# ComboSensorBreakout.net
KiCad netlist of a schematic drawn in EAGLE
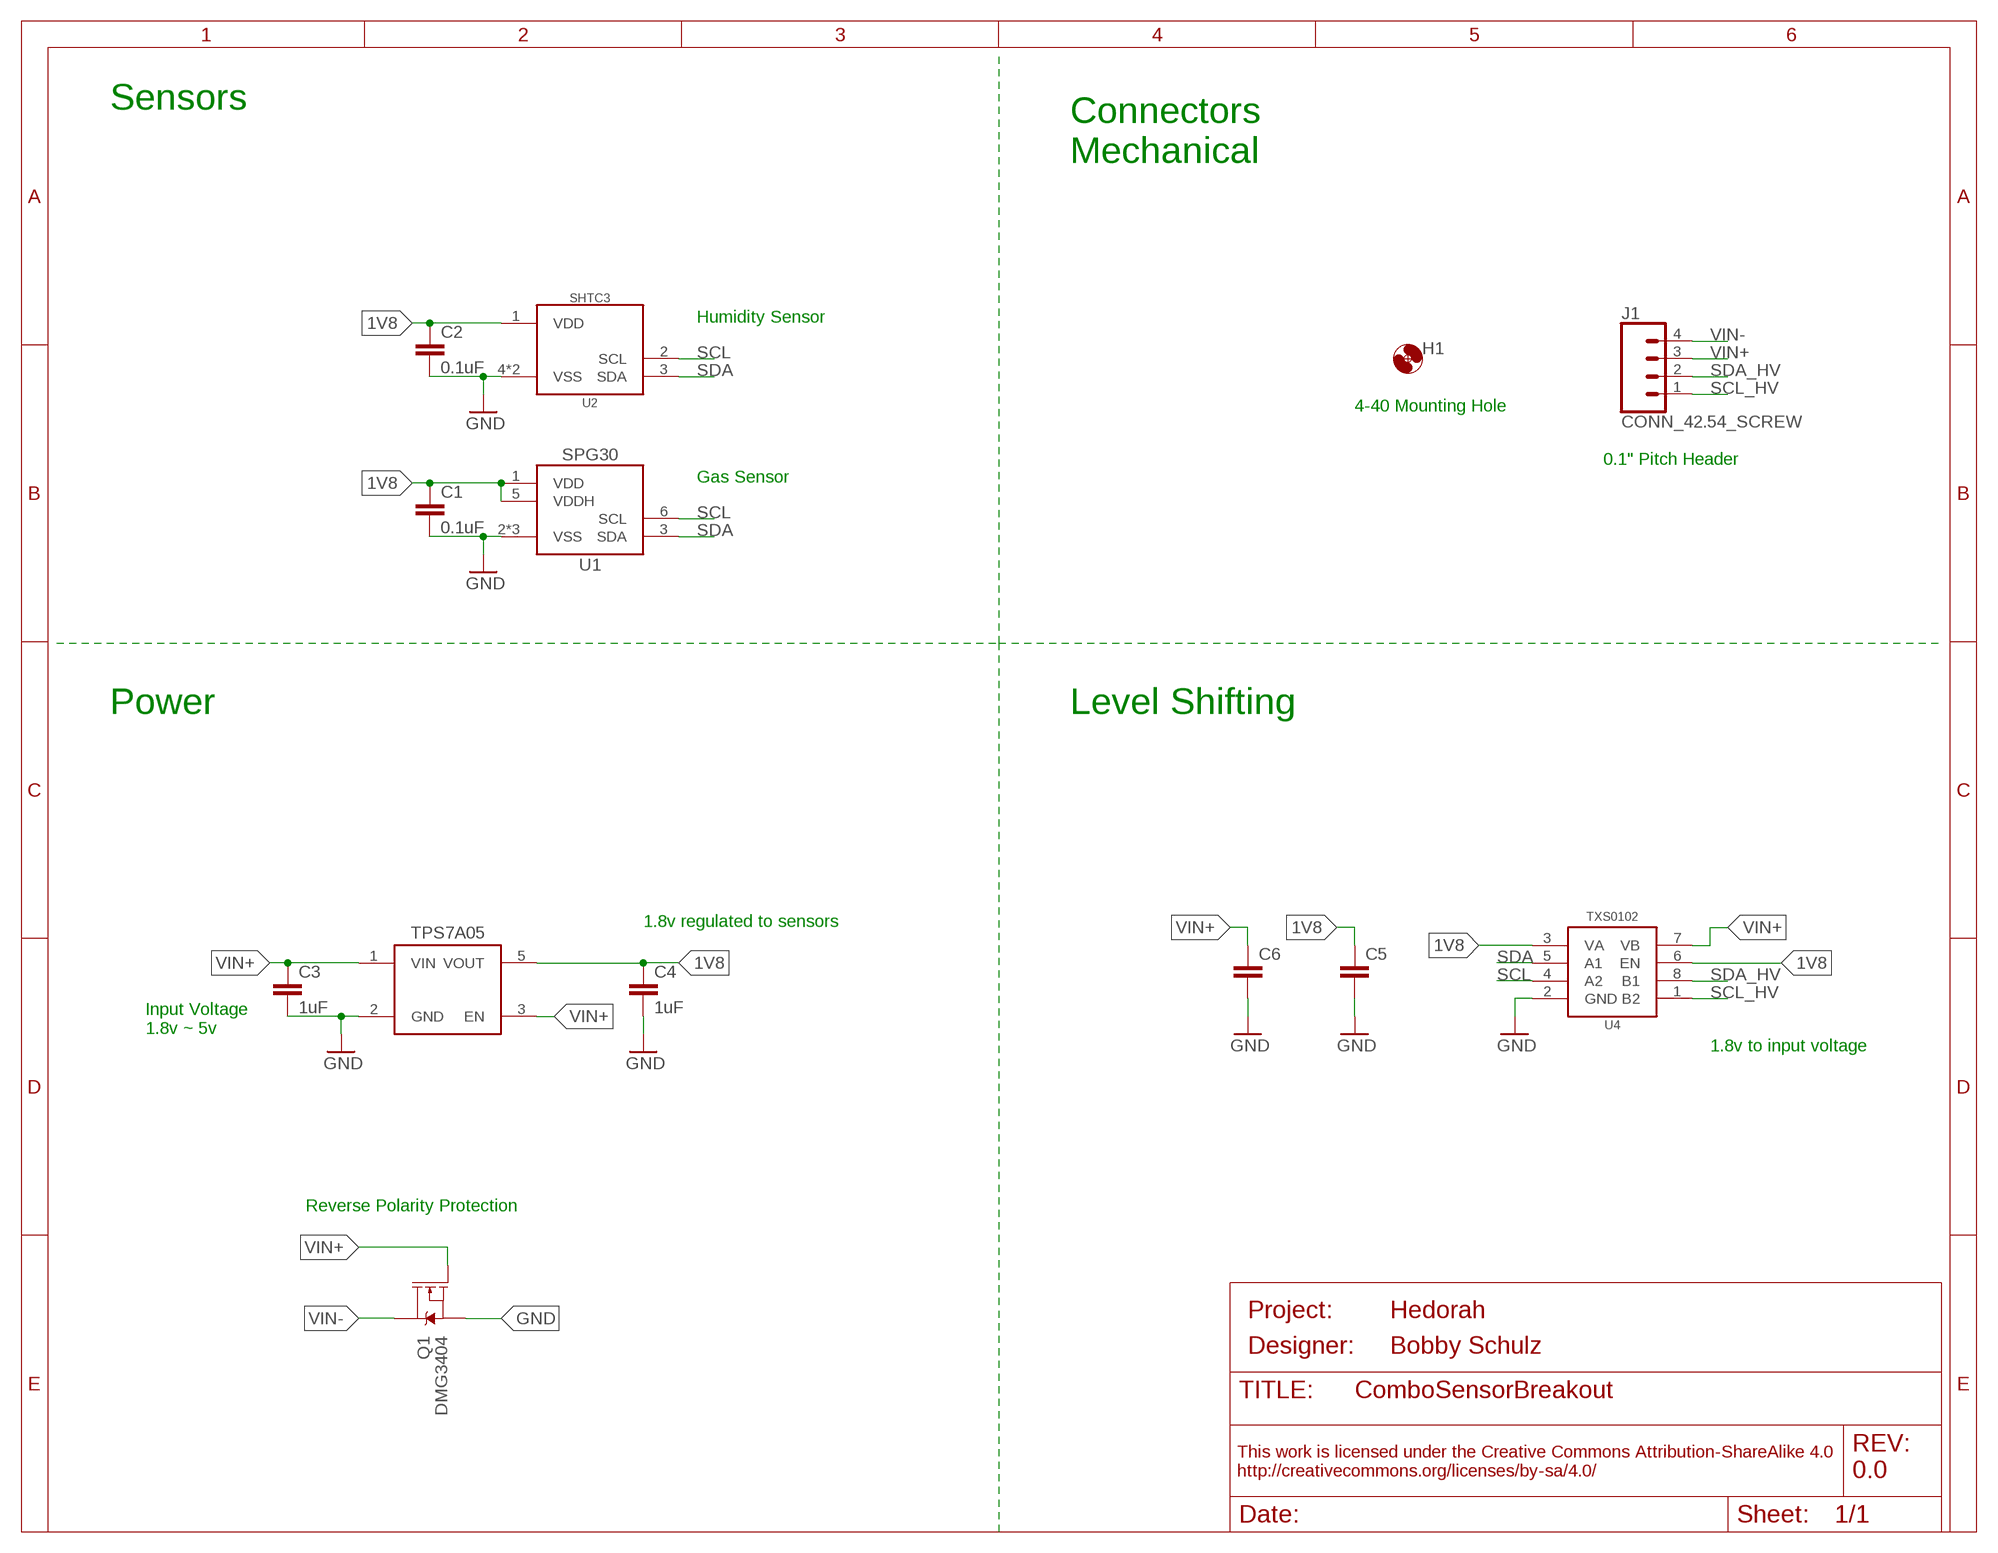
[diagram p0: schematic, sheet 1]

(export (version "E")
  (design (tool "Eeschema 10.0.6"))
  (components
    (comp (ref "C1")
      (value "0.1uF")
      (footprint "eagle-import:C0603")
      (fields (field (name "MF") "Murata") (field (name "MPN") "GCM188R71E104KA57D"))
      (libsource (lib "eagle-import") (part "C-EUC06030.1UF"))
    )
    (comp (ref "C2")
      (value "0.1uF")
      (footprint "eagle-import:C0603")
      (fields (field (name "MF") "Murata") (field (name "MPN") "GCM188R71E104KA57D"))
      (libsource (lib "eagle-import") (part "C-EUC06030.1UF"))
    )
    (comp (ref "C3")
      (value "1uF")
      (footprint "eagle-import:C0603")
      (fields (field (name "MF") "Murata") (field (name "MPN") "GRM188R61C105KA12D"))
      (libsource (lib "eagle-import") (part "C-EUC06031UF"))
    )
    (comp (ref "C4")
      (value "1uF")
      (footprint "eagle-import:C0603")
      (fields (field (name "MF") "Murata") (field (name "MPN") "GRM188R61C105KA12D"))
      (libsource (lib "eagle-import") (part "C-EUC06031UF"))
    )
    (comp (ref "C5")
      (value "C-EU0.1UFC0603")
      (footprint "eagle-import:C0603")
      (fields (field (name "MF") "Murata") (field (name "MPN") "GCM188R71E104KA57D"))
      (libsource (lib "eagle-import") (part "C-EUC06030.1UF"))
    )
    (comp (ref "C6")
      (value "C-EU0.1UFC0603")
      (footprint "eagle-import:C0603")
      (fields (field (name "MF") "Murata") (field (name "MPN") "GCM188R71E104KA57D"))
      (libsource (lib "eagle-import") (part "C-EUC06030.1UF"))
    )
    (comp (ref "H1")
      (value "MOUNTING_HOLE4_NP")
      (footprint "eagle-import:4_40")
      (libsource (lib "eagle-import") (part "MOUNTING_HOLE4_NP"))
    )
    (comp (ref "J1")
      (value "CONN_42.54_SCREW")
      (footprint "eagle-import:1X04_SCREW")
      (fields (field (name "MF") "On Shore") (field (name "MPN") "OSTVN04A150"))
      (libsource (lib "eagle-import") (part "CONN_42.54_SCREW"))
    )
    (comp (ref "Q1")
      (value "DMG3404")
      (footprint "eagle-import:SOT23-3")
      (fields (field (name "MF") "Diodes Incorporated") (field (name "MPN") "DMG3404L-7"))
      (libsource (lib "eagle-import") (part "MOSFET-NCH-DMG3404L"))
    )
    (comp (ref "U1")
      (value "SPG30")
      (footprint "eagle-import:DFN_6_2.5X2.5")
      (fields (field (name "MF") "Sensirion") (field (name "MPN") "SGP30-2.5K"))
      (libsource (lib "eagle-import") (part "SPG30"))
    )
    (comp (ref "U2")
      (value "SHTC3DFN")
      (footprint "eagle-import:DFN_4_2X2")
      (fields (field (name "DISP") "SHTC3") (field (name "MF") "Sensirion") (field (name "MPN") "SHTC3"))
      (libsource (lib "eagle-import") (part "SHTCDFN3"))
    )
    (comp (ref "U3")
      (value "TPS7A0518DBV")
      (footprint "eagle-import:SOT23-5")
      (fields (field (name "MF") "TI") (field (name "MPN") "TPS7A0518PDBVR"))
      (libsource (lib "eagle-import") (part "TPS7A05DBV18"))
    )
    (comp (ref "U4")
      (value "TXS0102DCU")
      (footprint "eagle-import:DCU_(R-PDSO-G8)")
      (fields (field (name "MF") "TI") (field (name "MPN") "TXS0102DCUR"))
      (libsource (lib "eagle-import") (part "TXS0102DCU"))
    )
  )
  (nets
    (net (code "1") (name "/SCL") (class "Default")
      (node (ref "U1") (pin "6") (pinfunction "SCL_6") (pintype "input"))
      (node (ref "U2") (pin "2") (pinfunction "SCL_2") (pintype "input"))
      (node (ref "U4") (pin "4") (pinfunction "A2_4") (pintype "bidirectional"))
    )
    (net (code "2") (name "/SCL_HV") (class "Default")
      (node (ref "J1") (pin "1") (pinfunction "1_1") (pintype "passive"))
      (node (ref "U4") (pin "1") (pinfunction "B2_1") (pintype "bidirectional"))
    )
    (net (code "3") (name "/SDA") (class "Default")
      (node (ref "U1") (pin "3") (pinfunction "SDA_3") (pintype "bidirectional"))
      (node (ref "U2") (pin "3") (pinfunction "SDA_3") (pintype "bidirectional"))
      (node (ref "U4") (pin "5") (pinfunction "A1_5") (pintype "bidirectional"))
    )
    (net (code "4") (name "/SDA_HV") (class "Default")
      (node (ref "J1") (pin "2") (pinfunction "2_2") (pintype "passive"))
      (node (ref "U4") (pin "8") (pinfunction "B1_8") (pintype "bidirectional"))
    )
    (net (code "5") (name "1V8") (class "Default")
      (node (ref "C1") (pin "1") (pinfunction "1_1") (pintype "passive"))
      (node (ref "C2") (pin "1") (pinfunction "1_1") (pintype "passive"))
      (node (ref "C4") (pin "1") (pinfunction "1_1") (pintype "passive"))
      (node (ref "C5") (pin "1") (pinfunction "1_1") (pintype "passive"))
      (node (ref "U1") (pin "1") (pinfunction "VDD_1") (pintype "power_in"))
      (node (ref "U1") (pin "5") (pinfunction "VDDH_5") (pintype "power_in"))
      (node (ref "U2") (pin "1") (pinfunction "VDD_1") (pintype "power_in"))
      (node (ref "U3") (pin "5") (pinfunction "VOUT_5") (pintype "power_in"))
      (node (ref "U4") (pin "3") (pinfunction "VA_3") (pintype "power_in"))
      (node (ref "U4") (pin "6") (pinfunction "EN_6") (pintype "input"))
    )
    (net (code "6") (name "GND") (class "Default")
      (node (ref "C1") (pin "2") (pinfunction "2_2") (pintype "passive"))
      (node (ref "C2") (pin "2") (pinfunction "2_2") (pintype "passive"))
      (node (ref "C3") (pin "2") (pinfunction "2_2") (pintype "passive"))
      (node (ref "C4") (pin "2") (pinfunction "2_2") (pintype "passive"))
      (node (ref "C5") (pin "2") (pinfunction "2_2") (pintype "passive"))
      (node (ref "C6") (pin "2") (pinfunction "2_2") (pintype "passive"))
      (node (ref "Q1") (pin "2") (pinfunction "S_2") (pintype "bidirectional"))
      (node (ref "U1") (pin "2") (pinfunction "VSS_2") (pintype "power_in"))
      (node (ref "U1") (pin "4") (pinfunction "VSS_4") (pintype "power_in"))
      (node (ref "U1") (pin "EP") (pinfunction "VSS_EP") (pintype "power_in"))
      (node (ref "U2") (pin "4") (pinfunction "VSS_4") (pintype "power_in"))
      (node (ref "U2") (pin "EP") (pinfunction "VSS_EP") (pintype "power_in"))
      (node (ref "U3") (pin "2") (pinfunction "GND_2") (pintype "power_in"))
      (node (ref "U4") (pin "2") (pinfunction "GND_2") (pintype "power_in"))
    )
    (net (code "7") (name "VIN+") (class "Default")
      (node (ref "C3") (pin "1") (pinfunction "1_1") (pintype "passive"))
      (node (ref "C6") (pin "1") (pinfunction "1_1") (pintype "passive"))
      (node (ref "J1") (pin "3") (pinfunction "3_3") (pintype "passive"))
      (node (ref "Q1") (pin "1") (pinfunction "G_1") (pintype "bidirectional"))
      (node (ref "U3") (pin "1") (pinfunction "VIN_1") (pintype "power_in"))
      (node (ref "U3") (pin "3") (pinfunction "EN_3") (pintype "input"))
      (node (ref "U4") (pin "7") (pinfunction "VB_7") (pintype "power_in"))
    )
    (net (code "8") (name "VIN-") (class "Default")
      (node (ref "J1") (pin "4") (pinfunction "4_4") (pintype "passive"))
      (node (ref "Q1") (pin "3") (pinfunction "D_3") (pintype "bidirectional"))
    )
  )
)
